# Differential_Pair_Routing_with_IP_and_CM.net
KiCad netlist of a schematic drawn in Altium Designer
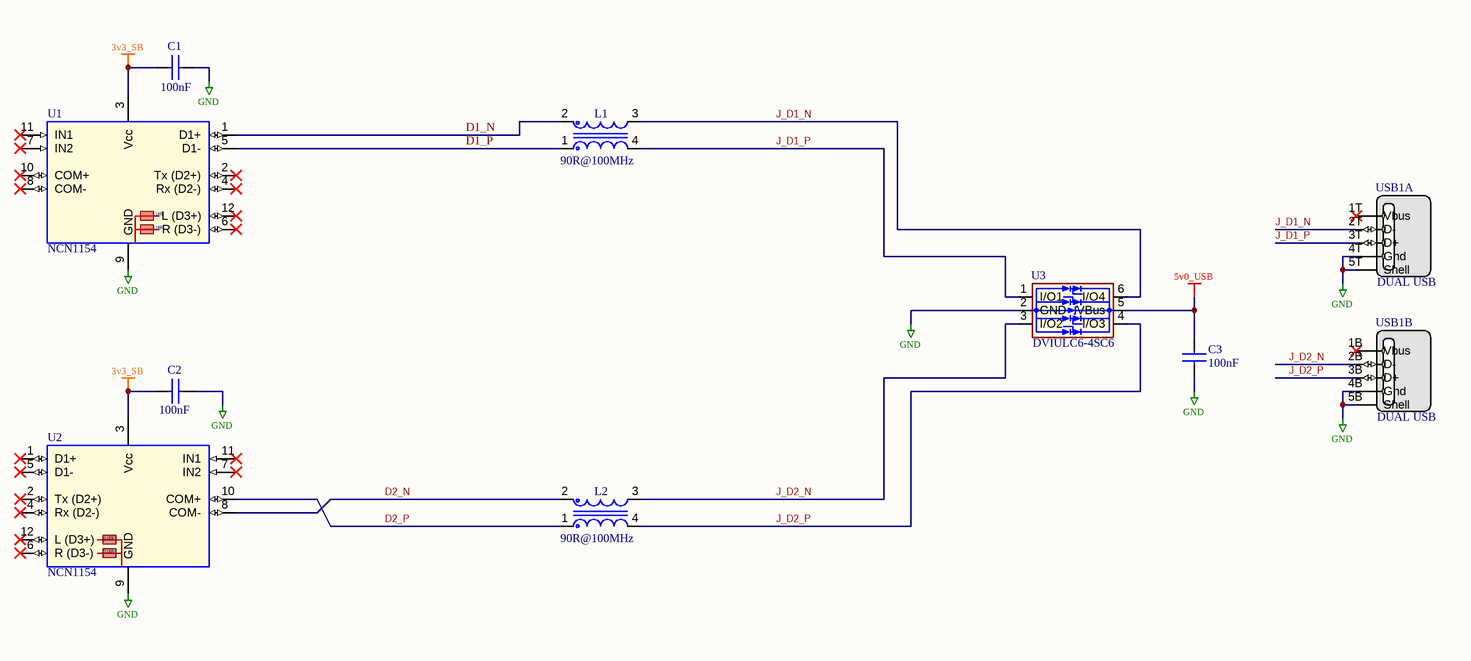
[diagram p0: Differential Pair Routing with IP and CM Setup.SchDoc]

(export (version "E")
  (design (tool "Eeschema 10.0.6"))
  (components
    (comp (ref "C1")
      (value "100nF")
      (footprint "CC0402")
      (description "Cap, 100nF, X7R, 16V, ±10%, CC0402")
      (libsource (lib "xSignal_Differential_Pairs") (part "CAP_100nF"))
    )
    (comp (ref "C2")
      (value "100nF")
      (footprint "CC0402")
      (description "Cap, 100nF, X7R, 16V, ±10%, CC0402")
      (libsource (lib "xSignal_Differential_Pairs") (part "CAP_100nF"))
    )
    (comp (ref "C3")
      (value "100nF")
      (footprint "CC0402")
      (description "Cap, 100nF, X7R, 16V, ±10%, CC0402")
      (libsource (lib "xSignal_Differential_Pairs") (part "CAP_100nF"))
    )
    (comp (ref "L1")
      (value "90R@100MHz")
      (footprint "ACM2012")
      (description "CMNCK, 90R@100MHz, 50V, 400mA, ACM2012")
      (libsource (lib "xSignal_Differential_Pairs") (part "FILTER"))
    )
    (comp (ref "L2")
      (value "90R@100MHz")
      (footprint "ACM2012")
      (description "CMNCK, 90R@100MHz, 50V, 400mA, ACM2012")
      (libsource (lib "xSignal_Differential_Pairs") (part "FILTER"))
    )
    (comp (ref "U1")
      (value "NCN1154")
      (footprint "UQFN12")
      (description "3:1 High-Speed USB /UART/Auido Mux")
      (libsource (lib "") (part "USB_UART_1"))
    )
    (comp (ref "U2")
      (value "NCN1154")
      (footprint "UQFN12")
      (description "3:1 High-Speed USB /UART/Auido Mux")
      (libsource (lib "xSignal_Differential_Pairs") (part "USB_UART"))
    )
    (comp (ref "U3")
      (value "DVIULC6-4SC6")
      (footprint "SOT23-6L")
      (description "4-chl Ultra-Low Capacitance ESD protector with TVS diode")
      (libsource (lib "xSignal_Differential_Pairs") (part "ESD_Protector"))
    )
    (comp (ref "USB1")
      (value "DUAL USB")
      (footprint "USB-A_RA_DUAL")
      (libsource (lib "xSignal_Differential_Pairs") (part "USB"))
    )
  )
  (nets
    (net (code "1") (name "/D1_N") (class "Default")
      (node (ref "L1") (pin "2") (pinfunction "2_2") (pintype "passive"))
      (node (ref "U1") (pin "1") (pinfunction "D1+_1") (pintype "bidirectional"))
    )
    (net (code "2") (name "/D1_P") (class "Default")
      (node (ref "L1") (pin "1") (pinfunction "1_1") (pintype "passive"))
      (node (ref "U1") (pin "5") (pinfunction "D1-_5") (pintype "bidirectional"))
    )
    (net (code "3") (name "/D2_N") (class "Default")
      (node (ref "L2") (pin "2") (pinfunction "2_2") (pintype "passive"))
      (node (ref "U2") (pin "8") (pinfunction "COM-_8") (pintype "bidirectional"))
    )
    (net (code "4") (name "/D2_P") (class "Default")
      (node (ref "L2") (pin "1") (pinfunction "1_1") (pintype "passive"))
      (node (ref "U2") (pin "10") (pinfunction "COM+_10") (pintype "bidirectional"))
    )
    (net (code "5") (name "/J_D1_N") (class "Default")
      (node (ref "L1") (pin "3") (pinfunction "3_3") (pintype "passive"))
      (node (ref "U3") (pin "6") (pinfunction "I/O4_6") (pintype "passive"))
      (node (ref "USB1") (pin "2T") (pinfunction "D-_2T") (pintype "bidirectional"))
    )
    (net (code "6") (name "/J_D1_P") (class "Default")
      (node (ref "L1") (pin "4") (pinfunction "4_4") (pintype "passive"))
      (node (ref "U3") (pin "1") (pinfunction "I/O1_1") (pintype "passive"))
      (node (ref "USB1") (pin "3T") (pinfunction "D+_3T") (pintype "bidirectional"))
    )
    (net (code "7") (name "/J_D2_N") (class "Default")
      (node (ref "L2") (pin "3") (pinfunction "3_3") (pintype "passive"))
      (node (ref "U3") (pin "3") (pinfunction "I/O2_3") (pintype "passive"))
      (node (ref "USB1") (pin "2B") (pinfunction "D-_2B") (pintype "bidirectional"))
    )
    (net (code "8") (name "/J_D2_P") (class "Default")
      (node (ref "L2") (pin "4") (pinfunction "4_4") (pintype "passive"))
      (node (ref "U3") (pin "4") (pinfunction "I/O3_4") (pintype "passive"))
      (node (ref "USB1") (pin "3B") (pinfunction "D+_3B") (pintype "bidirectional"))
    )
    (net (code "9") (name "3v3_SB") (class "Default")
      (node (ref "C1") (pin "2") (pinfunction "2_2") (pintype "passive"))
      (node (ref "C2") (pin "2") (pinfunction "2_2") (pintype "passive"))
      (node (ref "U1") (pin "3") (pinfunction "Vcc_3") (pintype "power_in"))
      (node (ref "U2") (pin "3") (pinfunction "Vcc_3") (pintype "power_in"))
    )
    (net (code "10") (name "5v0_USB") (class "Default")
      (node (ref "C3") (pin "1") (pinfunction "1_1") (pintype "passive"))
      (node (ref "U3") (pin "5") (pinfunction "VBus_5") (pintype "passive"))
    )
    (net (code "11") (name "GND") (class "Default")
      (node (ref "C1") (pin "1") (pinfunction "1_1") (pintype "passive"))
      (node (ref "C2") (pin "1") (pinfunction "1_1") (pintype "passive"))
      (node (ref "C3") (pin "2") (pinfunction "2_2") (pintype "passive"))
      (node (ref "U1") (pin "9") (pinfunction "GND_9") (pintype "power_in"))
      (node (ref "U2") (pin "9") (pinfunction "GND_9") (pintype "power_in"))
      (node (ref "U3") (pin "2") (pinfunction "GND_2") (pintype "passive"))
      (node (ref "USB1") (pin "4B") (pinfunction "Gnd_4B") (pintype "power_in"))
      (node (ref "USB1") (pin "4T") (pinfunction "Gnd_4T") (pintype "power_in"))
      (node (ref "USB1") (pin "5B") (pinfunction "Shell_5B") (pintype "power_in"))
      (node (ref "USB1") (pin "5T") (pinfunction "Shell_5T") (pintype "power_in"))
    )
    (net (code "12") (name "unconnected-(U1-COM+-Pad10)") (class "Default")
      (node (ref "U1") (pin "10") (pinfunction "COM+_10") (pintype "bidirectional+no_connect"))
    )
    (net (code "13") (name "unconnected-(U1-COM--Pad8)") (class "Default")
      (node (ref "U1") (pin "8") (pinfunction "COM-_8") (pintype "bidirectional+no_connect"))
    )
    (net (code "14") (name "unconnected-(U1-IN1-Pad11)") (class "Default")
      (node (ref "U1") (pin "11") (pinfunction "IN1_11") (pintype "input+no_connect"))
    )
    (net (code "15") (name "unconnected-(U1-IN2-Pad7)") (class "Default")
      (node (ref "U1") (pin "7") (pinfunction "IN2_7") (pintype "input+no_connect"))
    )
    (net (code "16") (name "unconnected-(U1-L_(D3+)-Pad12)") (class "Default")
      (node (ref "U1") (pin "12") (pinfunction "L_(D3+)_12") (pintype "bidirectional+no_connect"))
    )
    (net (code "17") (name "unconnected-(U1-R_(D3-)-Pad6)") (class "Default")
      (node (ref "U1") (pin "6") (pinfunction "R_(D3-)_6") (pintype "bidirectional+no_connect"))
    )
    (net (code "18") (name "unconnected-(U1-Rx_(D2-)-Pad4)") (class "Default")
      (node (ref "U1") (pin "4") (pinfunction "Rx_(D2-)_4") (pintype "bidirectional+no_connect"))
    )
    (net (code "19") (name "unconnected-(U1-Tx_(D2+)-Pad2)") (class "Default")
      (node (ref "U1") (pin "2") (pinfunction "Tx_(D2+)_2") (pintype "bidirectional+no_connect"))
    )
    (net (code "20") (name "unconnected-(U2-D1+-Pad1)") (class "Default")
      (node (ref "U2") (pin "1") (pinfunction "D1+_1") (pintype "bidirectional+no_connect"))
    )
    (net (code "21") (name "unconnected-(U2-D1--Pad5)") (class "Default")
      (node (ref "U2") (pin "5") (pinfunction "D1-_5") (pintype "bidirectional+no_connect"))
    )
    (net (code "22") (name "unconnected-(U2-IN1-Pad11)") (class "Default")
      (node (ref "U2") (pin "11") (pinfunction "IN1_11") (pintype "input+no_connect"))
    )
    (net (code "23") (name "unconnected-(U2-IN2-Pad7)") (class "Default")
      (node (ref "U2") (pin "7") (pinfunction "IN2_7") (pintype "input+no_connect"))
    )
    (net (code "24") (name "unconnected-(U2-L_(D3+)-Pad12)") (class "Default")
      (node (ref "U2") (pin "12") (pinfunction "L_(D3+)_12") (pintype "bidirectional+no_connect"))
    )
    (net (code "25") (name "unconnected-(U2-R_(D3-)-Pad6)") (class "Default")
      (node (ref "U2") (pin "6") (pinfunction "R_(D3-)_6") (pintype "bidirectional+no_connect"))
    )
    (net (code "26") (name "unconnected-(U2-Rx_(D2-)-Pad4)") (class "Default")
      (node (ref "U2") (pin "4") (pinfunction "Rx_(D2-)_4") (pintype "bidirectional+no_connect"))
    )
    (net (code "27") (name "unconnected-(U2-Tx_(D2+)-Pad2)") (class "Default")
      (node (ref "U2") (pin "2") (pinfunction "Tx_(D2+)_2") (pintype "bidirectional+no_connect"))
    )
    (net (code "28") (name "unconnected-(USB1A-Vbus-Pad1T)") (class "Default")
      (node (ref "USB1") (pin "1T") (pinfunction "Vbus_1T") (pintype "power_in+no_connect"))
    )
    (net (code "29") (name "unconnected-(USB1B-Vbus-Pad1B)") (class "Default")
      (node (ref "USB1") (pin "1B") (pinfunction "Vbus_1B") (pintype "power_in+no_connect"))
    )
  )
)
